# nb_watch.net
KiCad netlist of a schematic drawn in EasyEDA Pro
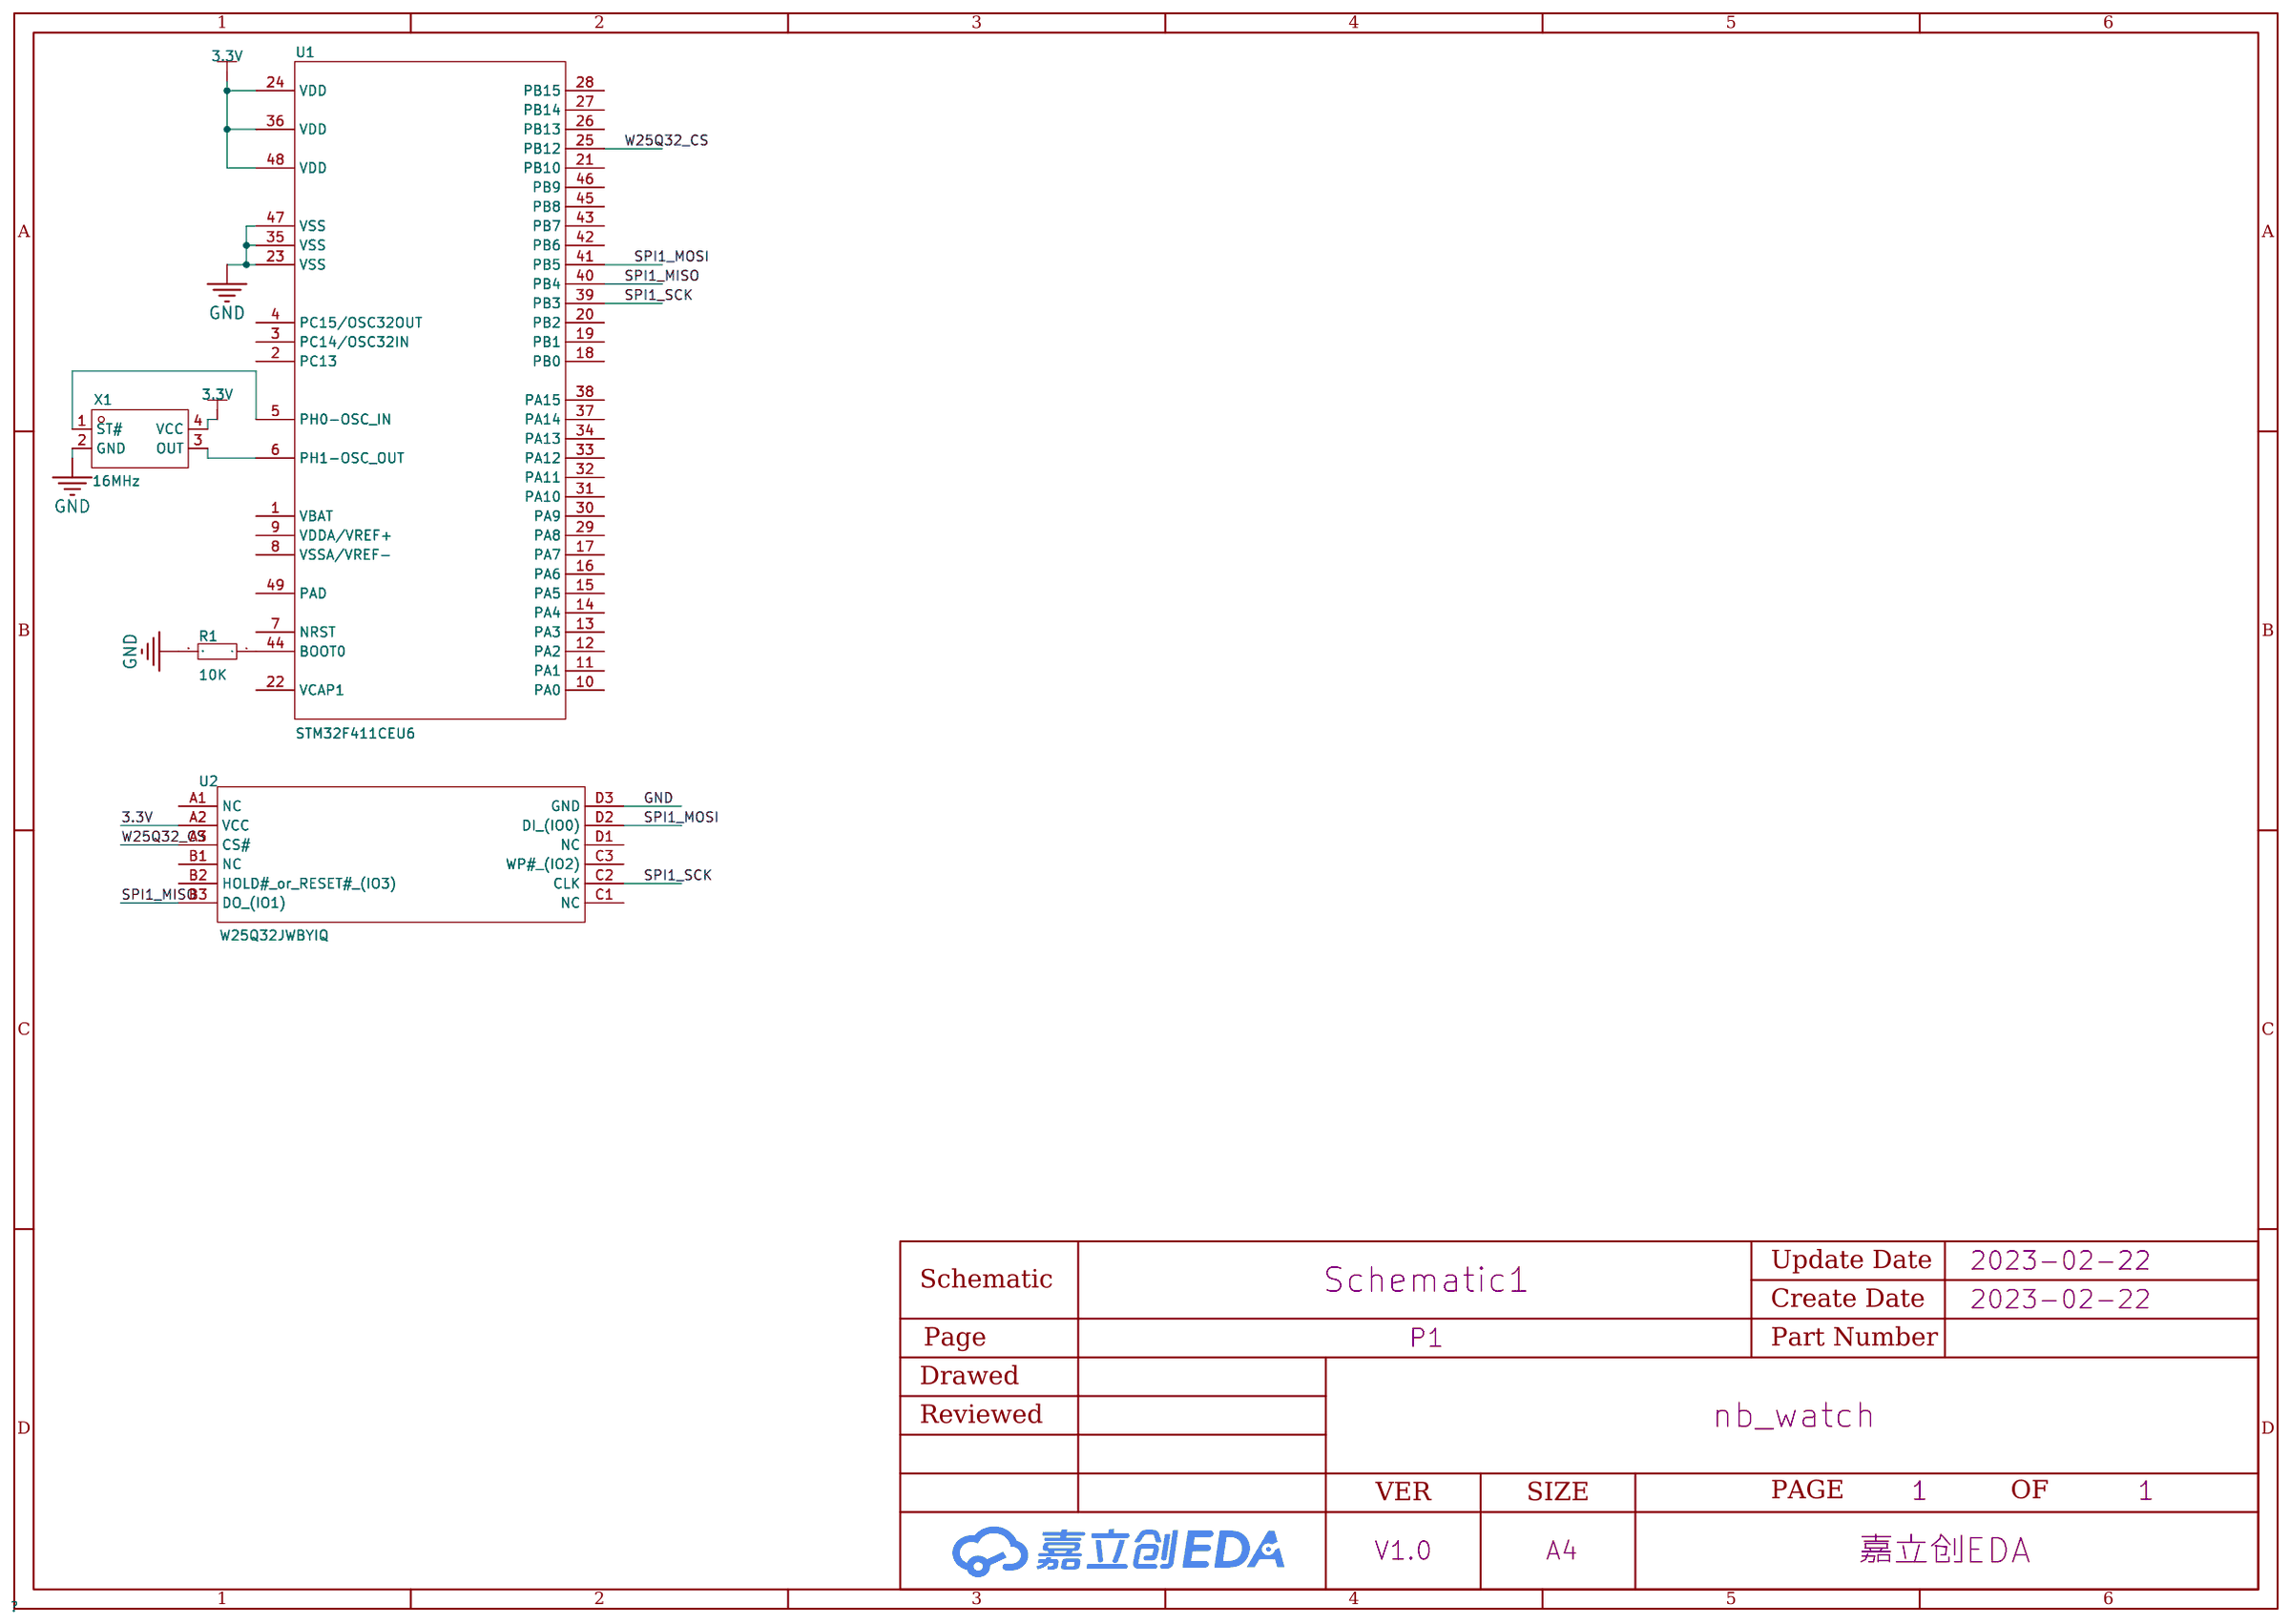
[diagram p0: schematic sheet]

(export (version "E")
  (design (tool "Eeschema 10.0.6"))
  (components
    (comp (ref "R1") (value "10K") (footprint "easyedapro:R0603") (libsource (lib "easyedapro") (part "电阻")))
    (comp (ref "U1")
      (value "STM32F411CEU6")
      (footprint "easyedapro:UFQFPN-48_L7.0-W7.0-P0.50-BL-EP")
      (fields (field (name "Manufacturer") "ST(意法半导体)"))
      (libsource (lib "easyedapro") (part "STM32F411CEU6"))
    )
    (comp (ref "U2")
      (value "W25Q32JWBYIQ")
      (footprint "easyedapro:WLCSP-12_L2.3-W2.0-R4-C3-P0.50-TL")
      (fields (field (name "Manufacturer") "WINBOND(华邦)"))
      (libsource (lib "easyedapro") (part "W25Q32JWBYIQ"))
    )
    (comp (ref "X1")
      (value "16MHz")
      (footprint "easyedapro:OSC-SMD_4P-L3.2-W2.5-BL")
      (description "工作电压:3.3V;工作电源电流（最大值）:2.5mA;主频:24MHz;")
      (fields (field (name "Manufacturer Part") "Q33310F70049000") (field (name "Manufacturer") "EPSON(爱普生)"))
      (libsource (lib "easyedapro") (part "Q33310F70049000"))
    )
  )
  (nets
    (net (code "1") (name "/SPI1_MISO") (class "Default")
      (node (ref "U1") (pin "40") (pinfunction "PB4_40") (pintype "input"))
      (node (ref "U2") (pin "B3") (pinfunction "DO_(IO1)_B3") (pintype "input"))
    )
    (net (code "2") (name "/SPI1_MOSI") (class "Default")
      (node (ref "U1") (pin "41") (pinfunction "PB5_41") (pintype "input"))
      (node (ref "U2") (pin "D2") (pinfunction "DI_(IO0)_D2") (pintype "input"))
    )
    (net (code "3") (name "/SPI1_SCK") (class "Default")
      (node (ref "U1") (pin "39") (pinfunction "PB3_39") (pintype "input"))
      (node (ref "U2") (pin "C2") (pinfunction "CLK_C2") (pintype "input"))
    )
    (net (code "4") (name "/W25Q32_CS") (class "Default")
      (node (ref "U1") (pin "25") (pinfunction "PB12_25") (pintype "input"))
      (node (ref "U2") (pin "A3") (pinfunction "CS#_A3") (pintype "input"))
    )
    (net (code "5") (name "3.3V") (class "Default")
      (node (ref "U1") (pin "24") (pinfunction "VDD_24") (pintype "input"))
      (node (ref "U1") (pin "36") (pinfunction "VDD_36") (pintype "input"))
      (node (ref "U1") (pin "48") (pinfunction "VDD_48") (pintype "input"))
      (node (ref "U2") (pin "A2") (pinfunction "VCC_A2") (pintype "input"))
      (node (ref "X1") (pin "4") (pinfunction "VCC_4") (pintype "input"))
    )
    (net (code "6") (name "GND") (class "Default")
      (node (ref "R1") (pin "2") (pinfunction "2_2") (pintype "input"))
      (node (ref "U1") (pin "23") (pinfunction "VSS_23") (pintype "input"))
      (node (ref "U1") (pin "35") (pinfunction "VSS_35") (pintype "input"))
      (node (ref "U1") (pin "47") (pinfunction "VSS_47") (pintype "input"))
      (node (ref "U2") (pin "D3") (pinfunction "GND_D3") (pintype "input"))
      (node (ref "X1") (pin "2") (pinfunction "GND_2") (pintype "input"))
    )
    (net (code "7") (name "Net-(U1-BOOT0)") (class "Default")
      (node (ref "R1") (pin "1") (pinfunction "1_1") (pintype "input"))
      (node (ref "U1") (pin "44") (pinfunction "BOOT0_44") (pintype "input"))
    )
    (net (code "8") (name "Net-(U1-PH0-OSC_IN)") (class "Default")
      (node (ref "U1") (pin "5") (pinfunction "PH0-OSC_IN_5") (pintype "input"))
      (node (ref "X1") (pin "1") (pinfunction "ST#_1") (pintype "input"))
    )
    (net (code "9") (name "Net-(U1-PH1-OSC_OUT)") (class "Default")
      (node (ref "U1") (pin "6") (pinfunction "PH1-OSC_OUT_6") (pintype "input"))
      (node (ref "X1") (pin "3") (pinfunction "OUT_3") (pintype "input"))
    )
    (net (code "10") (name "unconnected-(U1-NRST-Pad7)") (class "Default")
      (node (ref "U1") (pin "7") (pinfunction "NRST_7") (pintype "input"))
    )
    (net (code "11") (name "unconnected-(U1-PA0-Pad10)") (class "Default")
      (node (ref "U1") (pin "10") (pinfunction "PA0_10") (pintype "input"))
    )
    (net (code "12") (name "unconnected-(U1-PA1-Pad11)") (class "Default")
      (node (ref "U1") (pin "11") (pinfunction "PA1_11") (pintype "input"))
    )
    (net (code "13") (name "unconnected-(U1-PA2-Pad12)") (class "Default")
      (node (ref "U1") (pin "12") (pinfunction "PA2_12") (pintype "input"))
    )
    (net (code "14") (name "unconnected-(U1-PA3-Pad13)") (class "Default")
      (node (ref "U1") (pin "13") (pinfunction "PA3_13") (pintype "input"))
    )
    (net (code "15") (name "unconnected-(U1-PA4-Pad14)") (class "Default")
      (node (ref "U1") (pin "14") (pinfunction "PA4_14") (pintype "input"))
    )
    (net (code "16") (name "unconnected-(U1-PA5-Pad15)") (class "Default")
      (node (ref "U1") (pin "15") (pinfunction "PA5_15") (pintype "input"))
    )
    (net (code "17") (name "unconnected-(U1-PA6-Pad16)") (class "Default")
      (node (ref "U1") (pin "16") (pinfunction "PA6_16") (pintype "input"))
    )
    (net (code "18") (name "unconnected-(U1-PA7-Pad17)") (class "Default")
      (node (ref "U1") (pin "17") (pinfunction "PA7_17") (pintype "input"))
    )
    (net (code "19") (name "unconnected-(U1-PA8-Pad29)") (class "Default")
      (node (ref "U1") (pin "29") (pinfunction "PA8_29") (pintype "input"))
    )
    (net (code "20") (name "unconnected-(U1-PA9-Pad30)") (class "Default")
      (node (ref "U1") (pin "30") (pinfunction "PA9_30") (pintype "input"))
    )
    (net (code "21") (name "unconnected-(U1-PA10-Pad31)") (class "Default")
      (node (ref "U1") (pin "31") (pinfunction "PA10_31") (pintype "input"))
    )
    (net (code "22") (name "unconnected-(U1-PA11-Pad32)") (class "Default")
      (node (ref "U1") (pin "32") (pinfunction "PA11_32") (pintype "input"))
    )
    (net (code "23") (name "unconnected-(U1-PA12-Pad33)") (class "Default")
      (node (ref "U1") (pin "33") (pinfunction "PA12_33") (pintype "input"))
    )
    (net (code "24") (name "unconnected-(U1-PA13-Pad34)") (class "Default")
      (node (ref "U1") (pin "34") (pinfunction "PA13_34") (pintype "input"))
    )
    (net (code "25") (name "unconnected-(U1-PA14-Pad37)") (class "Default")
      (node (ref "U1") (pin "37") (pinfunction "PA14_37") (pintype "input"))
    )
    (net (code "26") (name "unconnected-(U1-PA15-Pad38)") (class "Default")
      (node (ref "U1") (pin "38") (pinfunction "PA15_38") (pintype "input"))
    )
    (net (code "27") (name "unconnected-(U1-PAD-Pad49)") (class "Default")
      (node (ref "U1") (pin "49") (pinfunction "PAD_49") (pintype "input"))
    )
    (net (code "28") (name "unconnected-(U1-PB0-Pad18)") (class "Default")
      (node (ref "U1") (pin "18") (pinfunction "PB0_18") (pintype "input"))
    )
    (net (code "29") (name "unconnected-(U1-PB1-Pad19)") (class "Default")
      (node (ref "U1") (pin "19") (pinfunction "PB1_19") (pintype "input"))
    )
    (net (code "30") (name "unconnected-(U1-PB2-Pad20)") (class "Default")
      (node (ref "U1") (pin "20") (pinfunction "PB2_20") (pintype "input"))
    )
    (net (code "31") (name "unconnected-(U1-PB6-Pad42)") (class "Default")
      (node (ref "U1") (pin "42") (pinfunction "PB6_42") (pintype "input"))
    )
    (net (code "32") (name "unconnected-(U1-PB7-Pad43)") (class "Default")
      (node (ref "U1") (pin "43") (pinfunction "PB7_43") (pintype "input"))
    )
    (net (code "33") (name "unconnected-(U1-PB8-Pad45)") (class "Default")
      (node (ref "U1") (pin "45") (pinfunction "PB8_45") (pintype "input"))
    )
    (net (code "34") (name "unconnected-(U1-PB9-Pad46)") (class "Default")
      (node (ref "U1") (pin "46") (pinfunction "PB9_46") (pintype "input"))
    )
    (net (code "35") (name "unconnected-(U1-PB10-Pad21)") (class "Default")
      (node (ref "U1") (pin "21") (pinfunction "PB10_21") (pintype "input"))
    )
    (net (code "36") (name "unconnected-(U1-PB13-Pad26)") (class "Default")
      (node (ref "U1") (pin "26") (pinfunction "PB13_26") (pintype "input"))
    )
    (net (code "37") (name "unconnected-(U1-PB14-Pad27)") (class "Default")
      (node (ref "U1") (pin "27") (pinfunction "PB14_27") (pintype "input"))
    )
    (net (code "38") (name "unconnected-(U1-PB15-Pad28)") (class "Default")
      (node (ref "U1") (pin "28") (pinfunction "PB15_28") (pintype "input"))
    )
    (net (code "39") (name "unconnected-(U1-PC13-Pad2)") (class "Default")
      (node (ref "U1") (pin "2") (pinfunction "PC13_2") (pintype "input"))
    )
    (net (code "40") (name "unconnected-(U1-PC14{slash}OSC32IN-Pad3)") (class "Default")
      (node (ref "U1") (pin "3") (pinfunction "PC14/OSC32IN_3") (pintype "input"))
    )
    (net (code "41") (name "unconnected-(U1-PC15{slash}OSC32OUT-Pad4)") (class "Default")
      (node (ref "U1") (pin "4") (pinfunction "PC15/OSC32OUT_4") (pintype "input"))
    )
    (net (code "42") (name "unconnected-(U1-VBAT-Pad1)") (class "Default")
      (node (ref "U1") (pin "1") (pinfunction "VBAT_1") (pintype "input"))
    )
    (net (code "43") (name "unconnected-(U1-VCAP1-Pad22)") (class "Default")
      (node (ref "U1") (pin "22") (pinfunction "VCAP1_22") (pintype "input"))
    )
    (net (code "44") (name "unconnected-(U1-VDDA{slash}VREF+-Pad9)") (class "Default")
      (node (ref "U1") (pin "9") (pinfunction "VDDA/VREF+_9") (pintype "input"))
    )
    (net (code "45") (name "unconnected-(U1-VSSA{slash}VREF--Pad8)") (class "Default")
      (node (ref "U1") (pin "8") (pinfunction "VSSA/VREF-_8") (pintype "input"))
    )
    (net (code "46") (name "unconnected-(U2-HOLD#_or_RESET#_(IO3)-PadB2)") (class "Default")
      (node (ref "U2") (pin "B2") (pinfunction "HOLD#_or_RESET#_(IO3)_B2") (pintype "input"))
    )
    (net (code "47") (name "unconnected-(U2-NC-PadA1)") (class "Default")
      (node (ref "U2") (pin "A1") (pinfunction "NC_A1") (pintype "input"))
    )
    (net (code "48") (name "unconnected-(U2-NC-PadB1)") (class "Default")
      (node (ref "U2") (pin "B1") (pinfunction "NC_B1") (pintype "input"))
    )
    (net (code "49") (name "unconnected-(U2-NC-PadC1)") (class "Default")
      (node (ref "U2") (pin "C1") (pinfunction "NC_C1") (pintype "input"))
    )
    (net (code "50") (name "unconnected-(U2-NC-PadD1)") (class "Default")
      (node (ref "U2") (pin "D1") (pinfunction "NC_D1") (pintype "input"))
    )
    (net (code "51") (name "unconnected-(U2-WP#_(IO2)-PadC3)") (class "Default")
      (node (ref "U2") (pin "C3") (pinfunction "WP#_(IO2)_C3") (pintype "input"))
    )
  )
)
